# compressor_contro0l.net
KiCad netlist of a schematic drawn in EAGLE
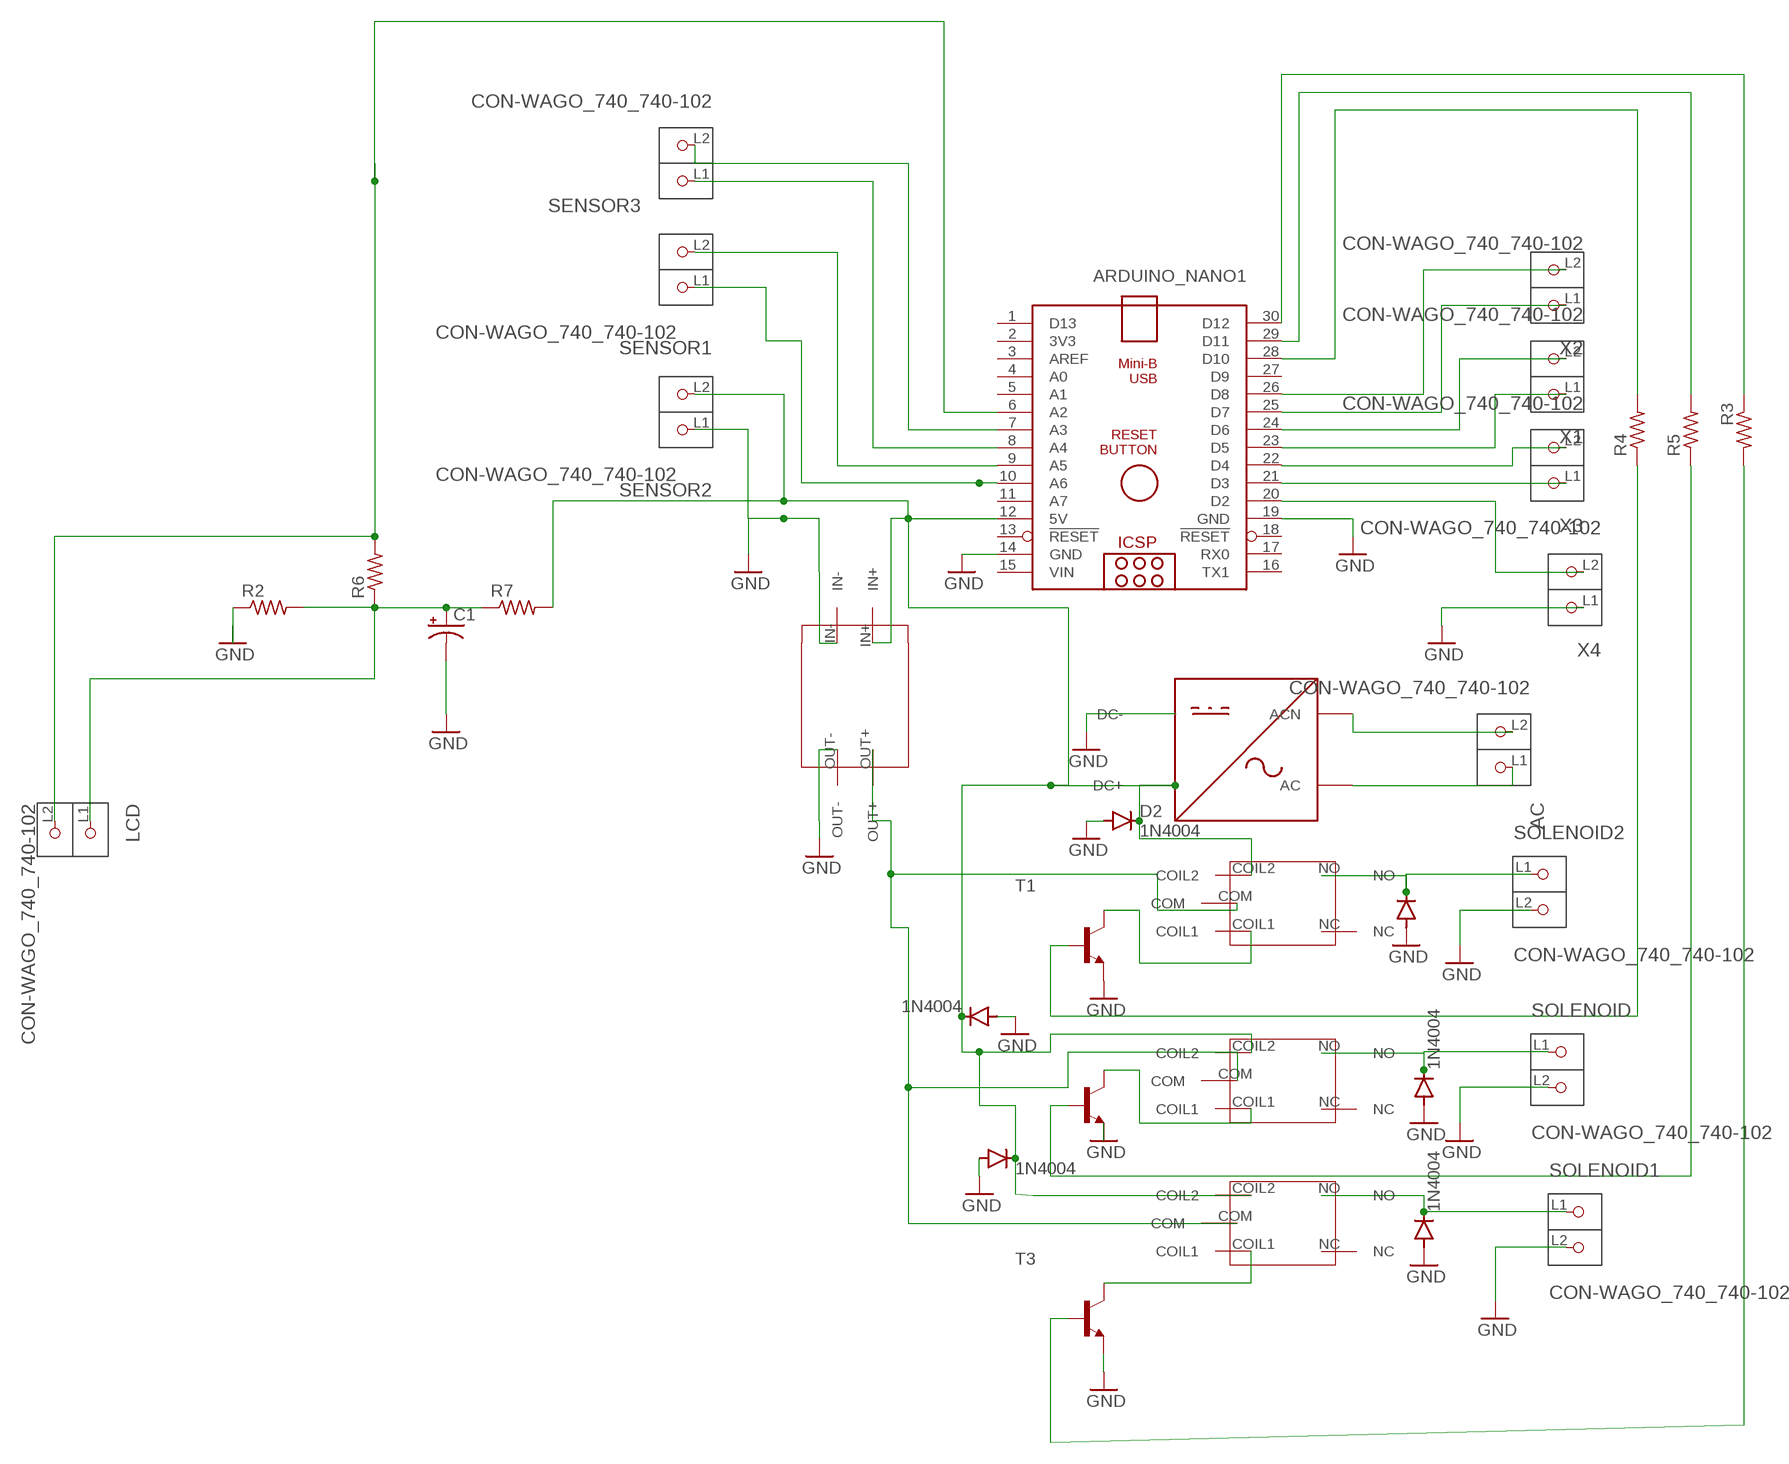
[diagram p0: schematic, sheet 1]

(export (version "E")
  (design (tool "Eeschema 10.0.6"))
  (components
    (comp (ref "AC")
      (value "CON-WAGO_740_740-102")
      (footprint "eagle-import:CON-WAGO_740_P-740-102")
      (libsource (lib "eagle-import") (part "CON-WAGO_740_740-102"))
    )
    (comp (ref "ACDC")
      (value "RPD10W1S")
      (footprint "eagle-import:2343")
      (libsource (lib "eagle-import") (part "RPD10W1S"))
    )
    (comp (ref "ARDUINO_NANO1")
      (value "ARDUINONANOV30-GHIT_ARDUINO_NANO")
      (footprint "eagle-import:ARDUINONANOV30-GHIT_ARDUINO_NANO")
      (libsource (lib "eagle-import") (part "ARDUINONANOV30-GHIT_ARDUINO_NANO"))
    )
    (comp (ref "C1")
      (value "CPOL-USE3.5-8")
      (footprint "eagle-import:E3,5-8")
      (libsource (lib "eagle-import") (part "CPOL-USE3.5-8"))
    )
    (comp (ref "D2")
      (value "1N4004")
      (footprint "eagle-import:DO41-10")
      (libsource (lib "eagle-import") (part "1N4004"))
    )
    (comp (ref "D3")
      (value "1N4004")
      (footprint "eagle-import:DO41-10")
      (libsource (lib "eagle-import") (part "1N4004"))
    )
    (comp (ref "D4")
      (value "1N4004")
      (footprint "eagle-import:DO41-10")
      (libsource (lib "eagle-import") (part "1N4004"))
    )
    (comp (ref "D5")
      (value "1N4004")
      (footprint "eagle-import:DO41-10")
      (libsource (lib "eagle-import") (part "1N4004"))
    )
    (comp (ref "D6")
      (value "1N4004")
      (footprint "eagle-import:DO41-10")
      (libsource (lib "eagle-import") (part "1N4004"))
    )
    (comp (ref "D7")
      (value "1N4004")
      (footprint "eagle-import:DO41-10")
      (libsource (lib "eagle-import") (part "1N4004"))
    )
    (comp (ref "LCD")
      (value "CON-WAGO_740_740-102")
      (footprint "eagle-import:CON-WAGO_740_P-740-102")
      (libsource (lib "eagle-import") (part "CON-WAGO_740_740-102"))
    )
    (comp (ref "R2")
      (value "R-US_0207/10")
      (footprint "eagle-import:0207_10")
      (libsource (lib "eagle-import") (part "rcl_334_R-US_0207/10"))
    )
    (comp (ref "R3")
      (value "R-US_0613/15")
      (footprint "eagle-import:P0613_15")
      (libsource (lib "eagle-import") (part "R-US_0613/15"))
    )
    (comp (ref "R4")
      (value "R-US_0613/15")
      (footprint "eagle-import:P0613_15")
      (libsource (lib "eagle-import") (part "R-US_0613/15"))
    )
    (comp (ref "R5")
      (value "R-US_0613/15")
      (footprint "eagle-import:P0613_15")
      (libsource (lib "eagle-import") (part "R-US_0613/15"))
    )
    (comp (ref "R6")
      (value "R-US_0207/10")
      (footprint "eagle-import:0207_10")
      (libsource (lib "eagle-import") (part "rcl_334_R-US_0207/10"))
    )
    (comp (ref "R7")
      (value "R-US_0207/10")
      (footprint "eagle-import:0207_10")
      (libsource (lib "eagle-import") (part "rcl_334_R-US_0207/10"))
    )
    (comp (ref "SENSOR1")
      (value "CON-WAGO_740_740-102")
      (footprint "eagle-import:CON-WAGO_740_P-740-102")
      (libsource (lib "eagle-import") (part "CON-WAGO_740_740-102"))
    )
    (comp (ref "SENSOR2")
      (value "CON-WAGO_740_740-102")
      (footprint "eagle-import:CON-WAGO_740_P-740-102")
      (libsource (lib "eagle-import") (part "CON-WAGO_740_740-102"))
    )
    (comp (ref "SENSOR3")
      (value "CON-WAGO_740_740-102")
      (footprint "eagle-import:CON-WAGO_740_P-740-102")
      (libsource (lib "eagle-import") (part "CON-WAGO_740_740-102"))
    )
    (comp (ref "SOLENOID")
      (value "CON-WAGO_740_740-102")
      (footprint "eagle-import:CON-WAGO_740_P-740-102")
      (libsource (lib "eagle-import") (part "CON-WAGO_740_740-102"))
    )
    (comp (ref "SOLENOID1")
      (value "CON-WAGO_740_740-102")
      (footprint "eagle-import:CON-WAGO_740_P-740-102")
      (libsource (lib "eagle-import") (part "CON-WAGO_740_740-102"))
    )
    (comp (ref "SOLENOID2")
      (value "CON-WAGO_740_740-102")
      (footprint "eagle-import:CON-WAGO_740_P-740-102")
      (libsource (lib "eagle-import") (part "CON-WAGO_740_740-102"))
    )
    (comp (ref "T1")
      (value "2N2222-NPN-TO92-EBC")
      (footprint "eagle-import:TO92-EBC")
      (libsource (lib "eagle-import") (part "-NPN-TO92-EBC2N2222"))
    )
    (comp (ref "T2")
      (value "2N2222-NPN-TO92-EBC")
      (footprint "eagle-import:TO92-EBC")
      (libsource (lib "eagle-import") (part "-NPN-TO92-EBC2N2222"))
    )
    (comp (ref "T3")
      (value "2N2222-NPN-TO92-EBC")
      (footprint "eagle-import:TO92-EBC")
      (libsource (lib "eagle-import") (part "-NPN-TO92-EBC2N2222"))
    )
    (comp (ref "U$2")
      (value "DC-DCBUCK")
      (footprint "eagle-import:DC-DCBUCK")
      (libsource (lib "eagle-import") (part "DC-DCBUCK"))
    )
    (comp (ref "U$3")
      (value "MRELAY2MRELAY2")
      (footprint "eagle-import:MRELAY")
      (libsource (lib "eagle-import") (part "MRELAY2MRELAY2"))
    )
    (comp (ref "U$4")
      (value "MRELAY2MRELAY2")
      (footprint "eagle-import:MRELAY")
      (libsource (lib "eagle-import") (part "MRELAY2MRELAY2"))
    )
    (comp (ref "U$5")
      (value "MRELAY2MRELAY2")
      (footprint "eagle-import:MRELAY")
      (libsource (lib "eagle-import") (part "MRELAY2MRELAY2"))
    )
    (comp (ref "X1")
      (value "CON-WAGO_740_740-102")
      (footprint "eagle-import:CON-WAGO_740_P-740-102")
      (libsource (lib "eagle-import") (part "CON-WAGO_740_740-102"))
    )
    (comp (ref "X2")
      (value "CON-WAGO_740_740-102")
      (footprint "eagle-import:CON-WAGO_740_P-740-102")
      (libsource (lib "eagle-import") (part "CON-WAGO_740_740-102"))
    )
    (comp (ref "X3")
      (value "CON-WAGO_740_740-102")
      (footprint "eagle-import:CON-WAGO_740_P-740-102")
      (libsource (lib "eagle-import") (part "CON-WAGO_740_740-102"))
    )
    (comp (ref "X4")
      (value "CON-WAGO_740_740-102")
      (footprint "eagle-import:CON-WAGO_740_P-740-102")
      (libsource (lib "eagle-import") (part "CON-WAGO_740_740-102"))
    )
  )
  (nets
    (net (code "1") (name "/VIN") (class "Default")
      (node (ref "ARDUINO_NANO1") (pin "15") (pinfunction "VIN_15") (pintype "power_in"))
    )
    (net (code "2") (name "GND") (class "Default")
      (node (ref "ACDC") (pin "DC-") (pinfunction "DC-_DC-") (pintype "bidirectional"))
      (node (ref "ARDUINO_NANO1") (pin "14") (pinfunction "GND_14") (pintype "power_in"))
      (node (ref "ARDUINO_NANO1") (pin "19") (pinfunction "GND_19") (pintype "power_in"))
      (node (ref "C1") (pin "-") (pinfunction "-_-") (pintype "passive"))
      (node (ref "D2") (pin "A") (pinfunction "A_A") (pintype "passive"))
      (node (ref "D3") (pin "A") (pinfunction "A_A") (pintype "passive"))
      (node (ref "D4") (pin "A") (pinfunction "A_A") (pintype "passive"))
      (node (ref "D5") (pin "A") (pinfunction "A_A") (pintype "passive"))
      (node (ref "D6") (pin "A") (pinfunction "A_A") (pintype "passive"))
      (node (ref "D7") (pin "A") (pinfunction "A_A") (pintype "passive"))
      (node (ref "R2") (pin "1") (pinfunction "1_1") (pintype "passive"))
      (node (ref "SENSOR2") (pin "L1") (pinfunction "P1_L1") (pintype "bidirectional"))
      (node (ref "SOLENOID") (pin "L2") (pinfunction "P2_L2") (pintype "bidirectional"))
      (node (ref "SOLENOID1") (pin "L2") (pinfunction "P2_L2") (pintype "bidirectional"))
      (node (ref "SOLENOID2") (pin "L2") (pinfunction "P2_L2") (pintype "bidirectional"))
      (node (ref "T1") (pin "E") (pinfunction "E_E") (pintype "passive"))
      (node (ref "T2") (pin "E") (pinfunction "E_E") (pintype "passive"))
      (node (ref "T3") (pin "E") (pinfunction "E_E") (pintype "passive"))
      (node (ref "U$2") (pin "IN-") (pinfunction "IN-_IN-") (pintype "bidirectional"))
      (node (ref "U$2") (pin "OUT-") (pinfunction "OUT-_OUT-") (pintype "bidirectional"))
      (node (ref "X4") (pin "L1") (pinfunction "P1_L1") (pintype "bidirectional"))
    )
    (net (code "3") (name "Net-(AC-P1)") (class "Default")
      (node (ref "AC") (pin "L1") (pinfunction "P1_L1") (pintype "bidirectional"))
      (node (ref "ACDC") (pin "AC") (pinfunction "AC_AC") (pintype "bidirectional"))
    )
    (net (code "4") (name "Net-(AC-P2)") (class "Default")
      (node (ref "AC") (pin "L2") (pinfunction "P2_L2") (pintype "bidirectional"))
      (node (ref "ACDC") (pin "ACN") (pinfunction "ACN_ACN") (pintype "bidirectional"))
    )
    (net (code "5") (name "Net-(ARDUINO_NANO1-5V)") (class "Default")
      (node (ref "ACDC") (pin "DC+") (pinfunction "DC+_DC+") (pintype "bidirectional"))
      (node (ref "ARDUINO_NANO1") (pin "12") (pinfunction "5V_12") (pintype "power_in"))
      (node (ref "D2") (pin "C") (pinfunction "C_C") (pintype "passive"))
      (node (ref "D4") (pin "C") (pinfunction "C_C") (pintype "passive"))
      (node (ref "D5") (pin "C") (pinfunction "C_C") (pintype "passive"))
      (node (ref "R7") (pin "2") (pinfunction "2_2") (pintype "passive"))
      (node (ref "SENSOR2") (pin "L2") (pinfunction "P2_L2") (pintype "bidirectional"))
      (node (ref "U$2") (pin "IN+") (pinfunction "IN+_IN+") (pintype "bidirectional"))
      (node (ref "U$3") (pin "COIL2") (pinfunction "COIL2_COIL2") (pintype "bidirectional"))
      (node (ref "U$4") (pin "COIL2") (pinfunction "COIL2_COIL2") (pintype "bidirectional"))
      (node (ref "U$5") (pin "COIL2") (pinfunction "COIL2_COIL2") (pintype "bidirectional"))
    )
    (net (code "6") (name "Net-(ARDUINO_NANO1-A2)") (class "Default")
      (node (ref "ARDUINO_NANO1") (pin "6") (pinfunction "A2_6") (pintype "bidirectional"))
      (node (ref "LCD") (pin "L2") (pinfunction "P2_L2") (pintype "bidirectional"))
      (node (ref "R6") (pin "2") (pinfunction "2_2") (pintype "passive"))
    )
    (net (code "7") (name "Net-(ARDUINO_NANO1-A3)") (class "Default")
      (node (ref "ARDUINO_NANO1") (pin "7") (pinfunction "A3_7") (pintype "bidirectional"))
      (node (ref "SENSOR3") (pin "L2") (pinfunction "P2_L2") (pintype "bidirectional"))
    )
    (net (code "8") (name "Net-(ARDUINO_NANO1-A4)") (class "Default")
      (node (ref "ARDUINO_NANO1") (pin "8") (pinfunction "A4_8") (pintype "bidirectional"))
      (node (ref "SENSOR3") (pin "L1") (pinfunction "P1_L1") (pintype "bidirectional"))
    )
    (net (code "9") (name "Net-(ARDUINO_NANO1-A5)") (class "Default")
      (node (ref "ARDUINO_NANO1") (pin "9") (pinfunction "A5_9") (pintype "bidirectional"))
      (node (ref "SENSOR1") (pin "L2") (pinfunction "P2_L2") (pintype "bidirectional"))
    )
    (net (code "10") (name "Net-(ARDUINO_NANO1-A6)") (class "Default")
      (node (ref "ARDUINO_NANO1") (pin "10") (pinfunction "A6_10") (pintype "bidirectional"))
      (node (ref "SENSOR1") (pin "L1") (pinfunction "P1_L1") (pintype "bidirectional"))
    )
    (net (code "11") (name "Net-(ARDUINO_NANO1-D2)") (class "Default")
      (node (ref "ARDUINO_NANO1") (pin "20") (pinfunction "D2_20") (pintype "bidirectional"))
      (node (ref "X4") (pin "L2") (pinfunction "P2_L2") (pintype "bidirectional"))
    )
    (net (code "12") (name "Net-(ARDUINO_NANO1-D3)") (class "Default")
      (node (ref "ARDUINO_NANO1") (pin "21") (pinfunction "D3_21") (pintype "bidirectional"))
      (node (ref "X3") (pin "L1") (pinfunction "P1_L1") (pintype "bidirectional"))
    )
    (net (code "13") (name "Net-(ARDUINO_NANO1-D4)") (class "Default")
      (node (ref "ARDUINO_NANO1") (pin "22") (pinfunction "D4_22") (pintype "bidirectional"))
      (node (ref "X3") (pin "L2") (pinfunction "P2_L2") (pintype "bidirectional"))
    )
    (net (code "14") (name "Net-(ARDUINO_NANO1-D5)") (class "Default")
      (node (ref "ARDUINO_NANO1") (pin "23") (pinfunction "D5_23") (pintype "bidirectional"))
      (node (ref "X1") (pin "L1") (pinfunction "P1_L1") (pintype "bidirectional"))
    )
    (net (code "15") (name "Net-(ARDUINO_NANO1-D6)") (class "Default")
      (node (ref "ARDUINO_NANO1") (pin "24") (pinfunction "D6_24") (pintype "bidirectional"))
      (node (ref "X1") (pin "L2") (pinfunction "P2_L2") (pintype "bidirectional"))
    )
    (net (code "16") (name "Net-(ARDUINO_NANO1-D7)") (class "Default")
      (node (ref "ARDUINO_NANO1") (pin "25") (pinfunction "D7_25") (pintype "bidirectional"))
      (node (ref "X2") (pin "L1") (pinfunction "P1_L1") (pintype "bidirectional"))
    )
    (net (code "17") (name "Net-(ARDUINO_NANO1-D8)") (class "Default")
      (node (ref "ARDUINO_NANO1") (pin "26") (pinfunction "D8_26") (pintype "bidirectional"))
      (node (ref "X2") (pin "L2") (pinfunction "P2_L2") (pintype "bidirectional"))
    )
    (net (code "18") (name "Net-(ARDUINO_NANO1-D10)") (class "Default")
      (node (ref "ARDUINO_NANO1") (pin "28") (pinfunction "D10_28") (pintype "bidirectional"))
      (node (ref "R4") (pin "2") (pinfunction "2_2") (pintype "passive"))
    )
    (net (code "19") (name "Net-(ARDUINO_NANO1-D11)") (class "Default")
      (node (ref "ARDUINO_NANO1") (pin "29") (pinfunction "D11_29") (pintype "bidirectional"))
      (node (ref "R5") (pin "2") (pinfunction "2_2") (pintype "passive"))
    )
    (net (code "20") (name "Net-(ARDUINO_NANO1-D12)") (class "Default")
      (node (ref "ARDUINO_NANO1") (pin "30") (pinfunction "D12_30") (pintype "bidirectional"))
      (node (ref "R3") (pin "1") (pinfunction "1_1") (pintype "passive"))
    )
    (net (code "21") (name "Net-(LCD-P1)") (class "Default")
      (node (ref "C1") (pin "+") (pinfunction "+_+") (pintype "passive"))
      (node (ref "LCD") (pin "L1") (pinfunction "P1_L1") (pintype "bidirectional"))
      (node (ref "R2") (pin "2") (pinfunction "2_2") (pintype "passive"))
      (node (ref "R6") (pin "1") (pinfunction "1_1") (pintype "passive"))
      (node (ref "R7") (pin "1") (pinfunction "1_1") (pintype "passive"))
    )
    (net (code "22") (name "Net-(R3-Pad2)") (class "Default")
      (node (ref "R3") (pin "2") (pinfunction "2_2") (pintype "passive"))
      (node (ref "T3") (pin "B") (pinfunction "B_B") (pintype "passive"))
    )
    (net (code "23") (name "Net-(R4-Pad1)") (class "Default")
      (node (ref "R4") (pin "1") (pinfunction "1_1") (pintype "passive"))
      (node (ref "T1") (pin "B") (pinfunction "B_B") (pintype "passive"))
    )
    (net (code "24") (name "Net-(R5-Pad1)") (class "Default")
      (node (ref "R5") (pin "1") (pinfunction "1_1") (pintype "passive"))
      (node (ref "T2") (pin "B") (pinfunction "B_B") (pintype "passive"))
    )
    (net (code "25") (name "Net-(SOLENOID-P1)") (class "Default")
      (node (ref "D3") (pin "C") (pinfunction "C_C") (pintype "passive"))
      (node (ref "SOLENOID") (pin "L1") (pinfunction "P1_L1") (pintype "bidirectional"))
      (node (ref "U$3") (pin "NO") (pinfunction "NO_NO") (pintype "bidirectional"))
    )
    (net (code "26") (name "Net-(SOLENOID1-P1)") (class "Default")
      (node (ref "D7") (pin "C") (pinfunction "C_C") (pintype "passive"))
      (node (ref "SOLENOID1") (pin "L1") (pinfunction "P1_L1") (pintype "bidirectional"))
      (node (ref "U$5") (pin "NO") (pinfunction "NO_NO") (pintype "bidirectional"))
    )
    (net (code "27") (name "Net-(SOLENOID2-P1)") (class "Default")
      (node (ref "D6") (pin "C") (pinfunction "C_C") (pintype "passive"))
      (node (ref "SOLENOID2") (pin "L1") (pinfunction "P1_L1") (pintype "bidirectional"))
      (node (ref "U$4") (pin "NO") (pinfunction "NO_NO") (pintype "bidirectional"))
    )
    (net (code "28") (name "Net-(T1-PadC)") (class "Default")
      (node (ref "T1") (pin "C") (pinfunction "C_C") (pintype "passive"))
      (node (ref "U$4") (pin "COIL1") (pinfunction "COIL1_COIL1") (pintype "bidirectional"))
    )
    (net (code "29") (name "Net-(T2-PadC)") (class "Default")
      (node (ref "T2") (pin "C") (pinfunction "C_C") (pintype "passive"))
      (node (ref "U$3") (pin "COIL1") (pinfunction "COIL1_COIL1") (pintype "bidirectional"))
    )
    (net (code "30") (name "Net-(T3-PadC)") (class "Default")
      (node (ref "T3") (pin "C") (pinfunction "C_C") (pintype "passive"))
      (node (ref "U$5") (pin "COIL1") (pinfunction "COIL1_COIL1") (pintype "bidirectional"))
    )
    (net (code "31") (name "Net-(U$2-PadOUT+)") (class "Default")
      (node (ref "U$2") (pin "OUT+") (pinfunction "OUT+_OUT+") (pintype "bidirectional"))
      (node (ref "U$3") (pin "COM") (pinfunction "COM_COM") (pintype "bidirectional"))
      (node (ref "U$4") (pin "COM") (pinfunction "COM_COM") (pintype "bidirectional"))
      (node (ref "U$5") (pin "COM") (pinfunction "COM_COM") (pintype "bidirectional"))
    )
    (net (code "32") (name "unconnected-(ARDUINO_NANO1-3V3-Pad2)") (class "Default")
      (node (ref "ARDUINO_NANO1") (pin "2") (pinfunction "3V3_2") (pintype "output"))
    )
    (net (code "33") (name "unconnected-(ARDUINO_NANO1-A0-Pad4)") (class "Default")
      (node (ref "ARDUINO_NANO1") (pin "4") (pinfunction "A0_4") (pintype "bidirectional"))
    )
    (net (code "34") (name "unconnected-(ARDUINO_NANO1-A1-Pad5)") (class "Default")
      (node (ref "ARDUINO_NANO1") (pin "5") (pinfunction "A1_5") (pintype "bidirectional"))
    )
    (net (code "35") (name "unconnected-(ARDUINO_NANO1-A7-Pad11)") (class "Default")
      (node (ref "ARDUINO_NANO1") (pin "11") (pinfunction "A7_11") (pintype "bidirectional"))
    )
    (net (code "36") (name "unconnected-(ARDUINO_NANO1-AREF-Pad3)") (class "Default")
      (node (ref "ARDUINO_NANO1") (pin "3") (pinfunction "AREF_3") (pintype "input"))
    )
    (net (code "37") (name "unconnected-(ARDUINO_NANO1-D9-Pad27)") (class "Default")
      (node (ref "ARDUINO_NANO1") (pin "27") (pinfunction "D9_27") (pintype "bidirectional"))
    )
    (net (code "38") (name "unconnected-(ARDUINO_NANO1-D13-Pad1)") (class "Default")
      (node (ref "ARDUINO_NANO1") (pin "1") (pinfunction "D13_1") (pintype "bidirectional"))
    )
    (net (code "39") (name "unconnected-(ARDUINO_NANO1-RX0-Pad17)") (class "Default")
      (node (ref "ARDUINO_NANO1") (pin "17") (pinfunction "RX0_17") (pintype "bidirectional"))
    )
    (net (code "40") (name "unconnected-(ARDUINO_NANO1-TX1-Pad16)") (class "Default")
      (node (ref "ARDUINO_NANO1") (pin "16") (pinfunction "TX1_16") (pintype "bidirectional"))
    )
    (net (code "41") (name "unconnected-(ARDUINO_NANO1-~{RESET}-Pad13)") (class "Default")
      (node (ref "ARDUINO_NANO1") (pin "13") (pinfunction "~{RESET}_13") (pintype "input"))
    )
    (net (code "42") (name "unconnected-(ARDUINO_NANO1-~{RESET}-Pad18)") (class "Default")
      (node (ref "ARDUINO_NANO1") (pin "18") (pinfunction "~{RESET}_18") (pintype "input"))
    )
    (net (code "43") (name "unconnected-(U$3-PadNC)") (class "Default")
      (node (ref "U$3") (pin "NC") (pinfunction "NC_NC") (pintype "bidirectional"))
    )
    (net (code "44") (name "unconnected-(U$4-PadNC)") (class "Default")
      (node (ref "U$4") (pin "NC") (pinfunction "NC_NC") (pintype "bidirectional"))
    )
    (net (code "45") (name "unconnected-(U$5-PadNC)") (class "Default")
      (node (ref "U$5") (pin "NC") (pinfunction "NC_NC") (pintype "bidirectional"))
    )
  )
)
